# snow_depth_gauge_2B.net
KiCad netlist of a schematic drawn in EAGLE
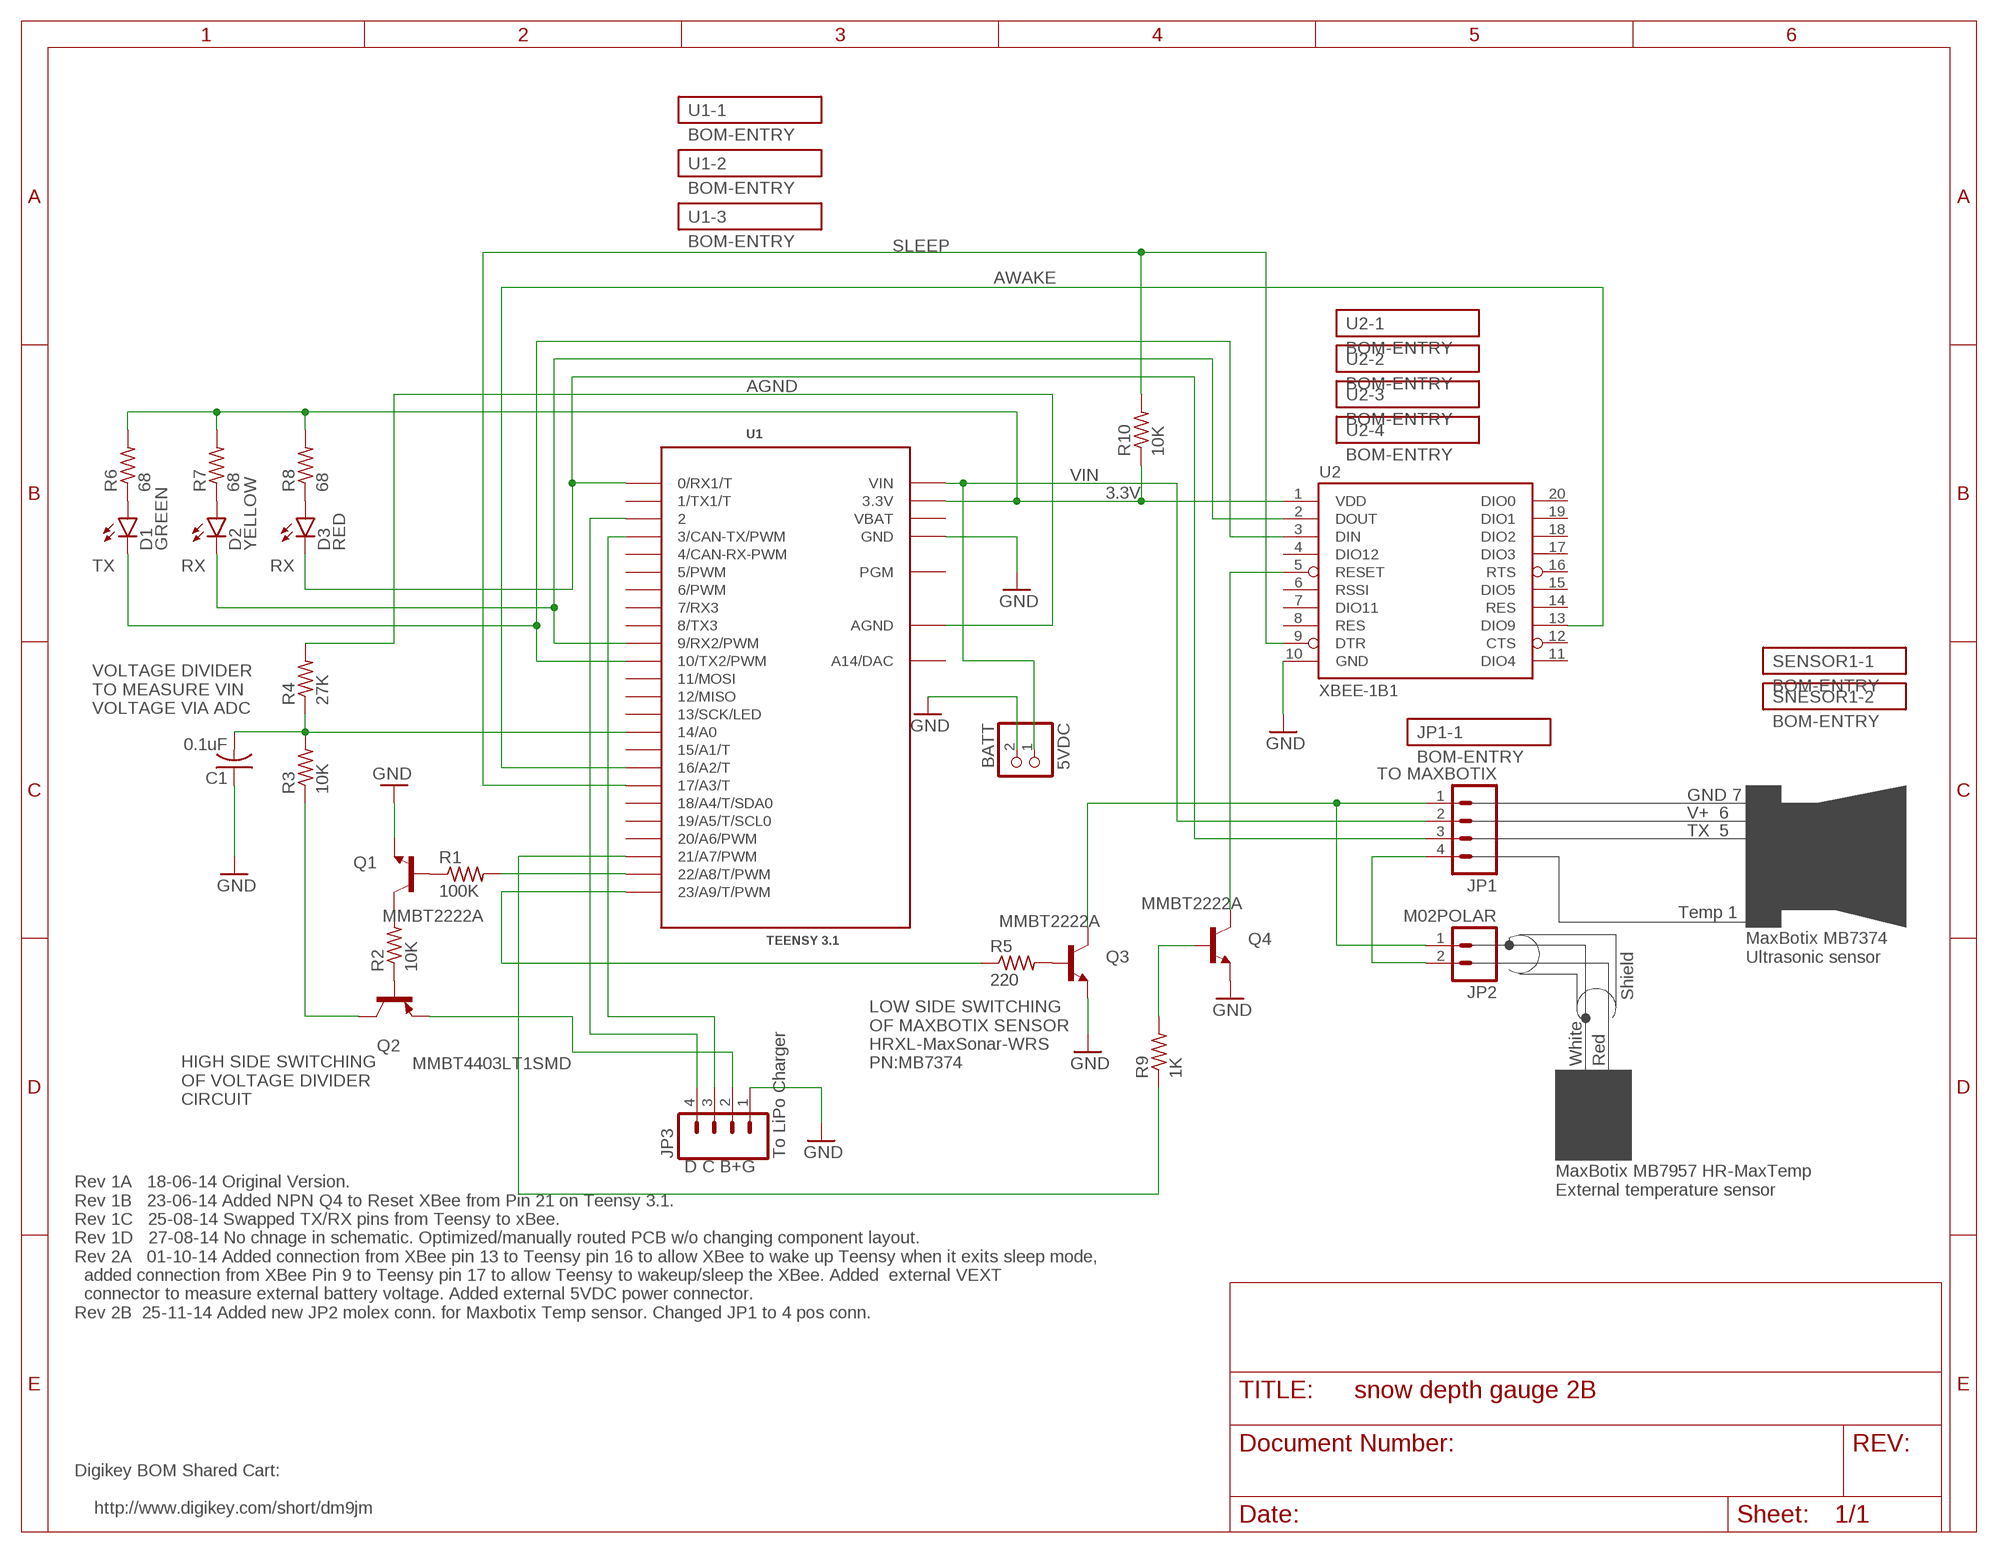
[diagram p0: schematic, sheet 1]

(export (version "E")
  (design (tool "Eeschema 10.0.6"))
  (components
    (comp (ref "BATT")
      (value "5VDC")
      (footprint "eagle-import:JST-PH-2-SMT-RA")
      (fields (field (name "PARTNO") "S2B-PH-SM4-TB(LF)(SN)"))
      (libsource (lib "eagle-import") (part "JST_2PIN-SMT-RA"))
    )
    (comp (ref "C1")
      (value "0.1uF")
      (footprint "eagle-import:C3216")
      (fields (field (name "PARTNO") "C1206C104K4RACTU"))
      (libsource (lib "eagle-import") (part "C-USC3216"))
    )
    (comp (ref "D1")
      (value "GREEN")
      (footprint "eagle-import:LED-0603")
      (fields (field (name "PARTNO") "LNJ337W83RA"))
      (libsource (lib "eagle-import") (part "LED-GREEN0603"))
    )
    (comp (ref "D2")
      (value "YELLOW")
      (footprint "eagle-import:LED-0603")
      (fields (field (name "PARTNO") "LNJ437W84RA"))
      (libsource (lib "eagle-import") (part "LED-YELLOW0603"))
    )
    (comp (ref "D3")
      (value "RED")
      (footprint "eagle-import:LED-0603")
      (fields (field (name "PARTNO") "LNJ237W82RA"))
      (libsource (lib "eagle-import") (part "LED-RED0603"))
    )
    (comp (ref "JP1")
      (value "TO MAXBOTIX")
      (footprint "eagle-import:MOLEX-1X4")
      (fields (field (name "PARTNO") "0022292041"))
      (libsource (lib "eagle-import") (part "M04POLAR"))
    )
    (comp (ref "JP2")
      (value "M02POLAR")
      (footprint "eagle-import:MOLEX-1X2")
      (fields (field (name "PARTNO") "0022292021"))
      (libsource (lib "eagle-import") (part "M02POLAR"))
    )
    (comp (ref "JP3")
      (value "To LiPo Charger")
      (footprint "eagle-import:MOLEX-1X4")
      (fields (field (name "PARTNO") "0022292041"))
      (libsource (lib "eagle-import") (part "M04POLAR"))
    )
    (comp (ref "Q1")
      (value "MMBT2222A")
      (footprint "eagle-import:SOT23-BEC")
      (libsource (lib "eagle-import") (part "-NPN-SOT23-BECMMBT2222ALT1"))
    )
    (comp (ref "Q2")
      (value "MMBT4403LT1SMD")
      (footprint "eagle-import:SOT23-BEC")
      (fields (field (name "PARTNO") "MMBT4403"))
      (libsource (lib "eagle-import") (part "MMBT4403SMDLT1"))
    )
    (comp (ref "Q3")
      (value "MMBT2222A")
      (footprint "eagle-import:SOT23-BEC")
      (libsource (lib "eagle-import") (part "-NPN-SOT23-BECMMBT2222ALT1"))
    )
    (comp (ref "Q4")
      (value "MMBT2222A")
      (footprint "eagle-import:SOT23-BEC")
      (libsource (lib "eagle-import") (part "-NPN-SOT23-BECMMBT2222ALT1"))
    )
    (comp (ref "R1")
      (value "100K")
      (footprint "eagle-import:R3216")
      (fields (field (name "PARTNO") "KTR18EZPJ104"))
      (libsource (lib "eagle-import") (part "R-US_R3216"))
    )
    (comp (ref "R2")
      (value "10K")
      (footprint "eagle-import:R3216")
      (fields (field (name "PARTNO") "KTR18EZPJ103"))
      (libsource (lib "eagle-import") (part "R-US_R3216"))
    )
    (comp (ref "R3")
      (value "10K")
      (footprint "eagle-import:R3216")
      (fields (field (name "PARTNO") "KTR18EZPJ103"))
      (libsource (lib "eagle-import") (part "R-US_R3216"))
    )
    (comp (ref "R4")
      (value "27K")
      (footprint "eagle-import:R3216")
      (fields (field (name "PARTNO") "KTR18EZPJ273"))
      (libsource (lib "eagle-import") (part "R-US_R3216"))
    )
    (comp (ref "R5")
      (value "220")
      (footprint "eagle-import:R3216")
      (fields (field (name "PARTNO") "KTR18EZPJ221"))
      (libsource (lib "eagle-import") (part "R-US_R3216"))
    )
    (comp (ref "R6")
      (value "68")
      (footprint "eagle-import:R3216")
      (fields (field (name "PARTNO") "KTR18EZPJ680"))
      (libsource (lib "eagle-import") (part "R-US_R3216"))
    )
    (comp (ref "R7")
      (value "68")
      (footprint "eagle-import:R3216")
      (fields (field (name "PARTNO") "KTR18EZPJ680"))
      (libsource (lib "eagle-import") (part "R-US_R3216"))
    )
    (comp (ref "R8")
      (value "68")
      (footprint "eagle-import:R3216")
      (fields (field (name "PARTNO") "KTR18EZPJ680"))
      (libsource (lib "eagle-import") (part "R-US_R3216"))
    )
    (comp (ref "R9")
      (value "1K")
      (footprint "eagle-import:R3216")
      (fields (field (name "PARTNO") "KTR18EZPJ102"))
      (libsource (lib "eagle-import") (part "R-US_R3216"))
    )
    (comp (ref "R10")
      (value "10K")
      (footprint "eagle-import:R3216")
      (fields (field (name "PARTNO") "KTR18EZPJ103"))
      (libsource (lib "eagle-import") (part "R-US_R3216"))
    )
    (comp (ref "U1")
      (value "TEENSY 3.1")
      (footprint "eagle-import:TEENSY_3.1_BASIC")
      (fields (field (name "PARTNO") "TEENSY31"))
      (libsource (lib "eagle-import") (part "TEENSY_3.1_BASIC"))
    )
    (comp (ref "U2")
      (value "XBEE-1B1")
      (footprint "eagle-import:XBEE-1")
      (fields (field (name "PARTNO") "XB24-AUI-001"))
      (libsource (lib "eagle-import") (part "XBEE-1B1"))
    )
  )
  (nets
    (net (code "1") (name "/3.3V") (class "Default")
      (node (ref "R10") (pin "1") (pinfunction "1_1") (pintype "passive"))
      (node (ref "R6") (pin "2") (pinfunction "2_2") (pintype "passive"))
      (node (ref "R7") (pin "2") (pinfunction "2_2") (pintype "passive"))
      (node (ref "R8") (pin "2") (pinfunction "2_2") (pintype "passive"))
      (node (ref "U1") (pin "3.3V") (pinfunction "3.3V_3.3V") (pintype "power_in"))
      (node (ref "U1") (pin "3.3V1") (pinfunction "3.3V_3.3V1") (pintype "power_in"))
      (node (ref "U2") (pin "1") (pinfunction "VDD_1") (pintype "power_in"))
    )
    (net (code "2") (name "/AGND") (class "Default")
      (node (ref "R4") (pin "2") (pinfunction "2_2") (pintype "passive"))
      (node (ref "U1") (pin "AGND") (pinfunction "AGND_AGND") (pintype "power_in"))
    )
    (net (code "3") (name "/AWAKE") (class "Default")
      (node (ref "U1") (pin "16/A2") (pinfunction "16/A2/T_16/A2") (pintype "bidirectional"))
      (node (ref "U2") (pin "13") (pinfunction "DIO9_13") (pintype "bidirectional"))
    )
    (net (code "4") (name "/SLEEP") (class "Default")
      (node (ref "R10") (pin "2") (pinfunction "2_2") (pintype "passive"))
      (node (ref "U1") (pin "17/A3") (pinfunction "17/A3/T_17/A3") (pintype "bidirectional"))
      (node (ref "U2") (pin "9") (pinfunction "DTR_9") (pintype "bidirectional"))
    )
    (net (code "5") (name "/VBAT") (class "Default")
      (node (ref "U1") (pin "VBAT") (pinfunction "VBAT_VBAT") (pintype "power_in"))
    )
    (net (code "6") (name "/VIN") (class "Default")
      (node (ref "BATT") (pin "1") (pinfunction "2_1") (pintype "passive"))
      (node (ref "JP1") (pin "2") (pinfunction "2_2") (pintype "passive"))
      (node (ref "U1") (pin "VIN") (pinfunction "VIN_VIN") (pintype "power_in"))
    )
    (net (code "7") (name "GND") (class "Default")
      (node (ref "BATT") (pin "2") (pinfunction "1_2") (pintype "passive"))
      (node (ref "C1") (pin "1") (pinfunction "1_1") (pintype "passive"))
      (node (ref "JP3") (pin "1") (pinfunction "1_1") (pintype "passive"))
      (node (ref "Q1") (pin "E") (pinfunction "E_E") (pintype "passive"))
      (node (ref "Q3") (pin "E") (pinfunction "E_E") (pintype "passive"))
      (node (ref "Q4") (pin "E") (pinfunction "E_E") (pintype "passive"))
      (node (ref "U1") (pin "GND") (pinfunction "GND_GND") (pintype "power_in"))
      (node (ref "U1") (pin "GND1") (pinfunction "GND_GND1") (pintype "power_in"))
      (node (ref "U2") (pin "10") (pinfunction "GND_10") (pintype "power_in"))
    )
    (net (code "8") (name "Net-(C1-Pad2)") (class "Default")
      (node (ref "C1") (pin "2") (pinfunction "2_2") (pintype "passive"))
      (node (ref "R3") (pin "2") (pinfunction "2_2") (pintype "passive"))
      (node (ref "R4") (pin "1") (pinfunction "1_1") (pintype "passive"))
      (node (ref "U1") (pin "14/A0") (pinfunction "14/A0_14/A0") (pintype "bidirectional"))
    )
    (net (code "9") (name "Net-(D1-PadA)") (class "Default")
      (node (ref "D1") (pin "A") (pinfunction "A_A") (pintype "passive"))
      (node (ref "R6") (pin "1") (pinfunction "1_1") (pintype "passive"))
    )
    (net (code "10") (name "Net-(D2-PadA)") (class "Default")
      (node (ref "D2") (pin "A") (pinfunction "A_A") (pintype "passive"))
      (node (ref "R7") (pin "1") (pinfunction "1_1") (pintype "passive"))
    )
    (net (code "11") (name "Net-(D3-PadA)") (class "Default")
      (node (ref "D3") (pin "A") (pinfunction "A_A") (pintype "passive"))
      (node (ref "R8") (pin "1") (pinfunction "1_1") (pintype "passive"))
    )
    (net (code "12") (name "Net-(JP1-Pad1)") (class "Default")
      (node (ref "JP1") (pin "1") (pinfunction "1_1") (pintype "passive"))
      (node (ref "JP2") (pin "1") (pinfunction "1_1") (pintype "passive"))
      (node (ref "Q3") (pin "C") (pinfunction "C_C") (pintype "passive"))
    )
    (net (code "13") (name "Net-(JP1-Pad4)") (class "Default")
      (node (ref "JP1") (pin "4") (pinfunction "4_4") (pintype "passive"))
      (node (ref "JP2") (pin "2") (pinfunction "2_2") (pintype "passive"))
    )
    (net (code "14") (name "Net-(JP3-Pad2)") (class "Default")
      (node (ref "JP3") (pin "2") (pinfunction "2_2") (pintype "passive"))
      (node (ref "Q2") (pin "E") (pinfunction "E_E") (pintype "passive"))
    )
    (net (code "15") (name "Net-(JP3-Pad4)") (class "Default")
      (node (ref "JP3") (pin "4") (pinfunction "4_4") (pintype "passive"))
      (node (ref "U1") (pin "2") (pinfunction "2_2") (pintype "bidirectional"))
    )
    (net (code "16") (name "Net-(Q1-PadB)") (class "Default")
      (node (ref "Q1") (pin "B") (pinfunction "B_B") (pintype "passive"))
      (node (ref "R1") (pin "1") (pinfunction "1_1") (pintype "passive"))
    )
    (net (code "17") (name "Net-(Q1-PadC)") (class "Default")
      (node (ref "Q1") (pin "C") (pinfunction "C_C") (pintype "passive"))
      (node (ref "R2") (pin "2") (pinfunction "2_2") (pintype "passive"))
    )
    (net (code "18") (name "Net-(Q2-PadB)") (class "Default")
      (node (ref "Q2") (pin "B") (pinfunction "B_B") (pintype "passive"))
      (node (ref "R2") (pin "1") (pinfunction "1_1") (pintype "passive"))
    )
    (net (code "19") (name "Net-(Q2-PadC)") (class "Default")
      (node (ref "Q2") (pin "C") (pinfunction "C_C") (pintype "passive"))
      (node (ref "R3") (pin "1") (pinfunction "1_1") (pintype "passive"))
    )
    (net (code "20") (name "Net-(Q3-PadB)") (class "Default")
      (node (ref "Q3") (pin "B") (pinfunction "B_B") (pintype "passive"))
      (node (ref "R5") (pin "2") (pinfunction "2_2") (pintype "passive"))
    )
    (net (code "21") (name "Net-(Q4-PadB)") (class "Default")
      (node (ref "Q4") (pin "B") (pinfunction "B_B") (pintype "passive"))
      (node (ref "R9") (pin "2") (pinfunction "2_2") (pintype "passive"))
    )
    (net (code "22") (name "Net-(U1-0{slash}RX1{slash}T)") (class "Default")
      (node (ref "D3") (pin "C") (pinfunction "C_C") (pintype "passive"))
      (node (ref "JP1") (pin "3") (pinfunction "3_3") (pintype "passive"))
      (node (ref "U1") (pin "0") (pinfunction "0/RX1/T_0") (pintype "bidirectional"))
    )
    (net (code "23") (name "Net-(U1-3{slash}CAN-TX{slash}PWM)") (class "Default")
      (node (ref "JP3") (pin "3") (pinfunction "3_3") (pintype "passive"))
      (node (ref "U1") (pin "3") (pinfunction "3/CAN-TX/PWM_3") (pintype "bidirectional"))
    )
    (net (code "24") (name "Net-(U1-9{slash}RX2{slash}PWM)") (class "Default")
      (node (ref "D2") (pin "C") (pinfunction "C_C") (pintype "passive"))
      (node (ref "U1") (pin "9") (pinfunction "9/RX2/PWM_9") (pintype "bidirectional"))
      (node (ref "U2") (pin "2") (pinfunction "DOUT_2") (pintype "output"))
    )
    (net (code "25") (name "Net-(U1-10{slash}TX2{slash}PWM)") (class "Default")
      (node (ref "D1") (pin "C") (pinfunction "C_C") (pintype "passive"))
      (node (ref "U1") (pin "10") (pinfunction "10/TX2/PWM_10") (pintype "bidirectional"))
      (node (ref "U2") (pin "3") (pinfunction "DIN_3") (pintype "input"))
    )
    (net (code "26") (name "Net-(U1-21{slash}A7{slash}PWM)") (class "Default")
      (node (ref "R9") (pin "1") (pinfunction "1_1") (pintype "passive"))
      (node (ref "U1") (pin "21/A7") (pinfunction "21/A7/PWM_21/A7") (pintype "bidirectional"))
    )
    (net (code "27") (name "Net-(U1-22{slash}A8{slash}T{slash}PWM)") (class "Default")
      (node (ref "R1") (pin "2") (pinfunction "2_2") (pintype "passive"))
      (node (ref "U1") (pin "22/A8") (pinfunction "22/A8/T/PWM_22/A8") (pintype "bidirectional"))
    )
    (net (code "28") (name "Net-(U1-23{slash}A9{slash}T{slash}PWM)") (class "Default")
      (node (ref "R5") (pin "1") (pinfunction "1_1") (pintype "passive"))
      (node (ref "U1") (pin "23/A9") (pinfunction "23/A9/T/PWM_23/A9") (pintype "bidirectional"))
    )
    (net (code "29") (name "Net-(U2-RESET)") (class "Default")
      (node (ref "Q4") (pin "C") (pinfunction "C_C") (pintype "passive"))
      (node (ref "U2") (pin "5") (pinfunction "RESET_5") (pintype "input"))
    )
    (net (code "30") (name "unconnected-(U1-1{slash}TX1{slash}T-Pad1)") (class "Default")
      (node (ref "U1") (pin "1") (pinfunction "1/TX1/T_1") (pintype "bidirectional"))
    )
    (net (code "31") (name "unconnected-(U1-4{slash}CAN-RX-PWM-Pad4)") (class "Default")
      (node (ref "U1") (pin "4") (pinfunction "4/CAN-RX-PWM_4") (pintype "bidirectional"))
    )
    (net (code "32") (name "unconnected-(U1-5{slash}PWM-Pad5)") (class "Default")
      (node (ref "U1") (pin "5") (pinfunction "5/PWM_5") (pintype "bidirectional"))
    )
    (net (code "33") (name "unconnected-(U1-6{slash}PWM-Pad6)") (class "Default")
      (node (ref "U1") (pin "6") (pinfunction "6/PWM_6") (pintype "bidirectional"))
    )
    (net (code "34") (name "unconnected-(U1-7{slash}RX3-Pad7)") (class "Default")
      (node (ref "U1") (pin "7") (pinfunction "7/RX3_7") (pintype "bidirectional"))
    )
    (net (code "35") (name "unconnected-(U1-8{slash}TX3-Pad8)") (class "Default")
      (node (ref "U1") (pin "8") (pinfunction "8/TX3_8") (pintype "bidirectional"))
    )
    (net (code "36") (name "unconnected-(U1-11{slash}MOSI-Pad11)") (class "Default")
      (node (ref "U1") (pin "11") (pinfunction "11/MOSI_11") (pintype "bidirectional"))
    )
    (net (code "37") (name "unconnected-(U1-12{slash}MISO-Pad12)") (class "Default")
      (node (ref "U1") (pin "12") (pinfunction "12/MISO_12") (pintype "bidirectional"))
    )
    (net (code "38") (name "unconnected-(U1-13{slash}SCK{slash}LED-Pad13)") (class "Default")
      (node (ref "U1") (pin "13") (pinfunction "13/SCK/LED_13") (pintype "bidirectional"))
    )
    (net (code "39") (name "unconnected-(U1-15{slash}A1{slash}T-Pad15{slash}A1)") (class "Default")
      (node (ref "U1") (pin "15/A1") (pinfunction "15/A1/T_15/A1") (pintype "bidirectional"))
    )
    (net (code "40") (name "unconnected-(U1-18{slash}A4{slash}T{slash}SDA0-Pad18{slash}A4)") (class "Default")
      (node (ref "U1") (pin "18/A4") (pinfunction "18/A4/T/SDA0_18/A4") (pintype "bidirectional"))
    )
    (net (code "41") (name "unconnected-(U1-19{slash}A5{slash}T{slash}SCL0-Pad19{slash}A5)") (class "Default")
      (node (ref "U1") (pin "19/A5") (pinfunction "19/A5/T/SCL0_19/A5") (pintype "bidirectional"))
    )
    (net (code "42") (name "unconnected-(U1-20{slash}A6{slash}PWM-Pad20{slash}A6)") (class "Default")
      (node (ref "U1") (pin "20/A6") (pinfunction "20/A6/PWM_20/A6") (pintype "bidirectional"))
    )
    (net (code "43") (name "unconnected-(U1-A14{slash}DAC-PadA14)") (class "Default")
      (node (ref "U1") (pin "A14") (pinfunction "A14/DAC_A14") (pintype "bidirectional"))
    )
    (net (code "44") (name "unconnected-(U1-PadPGM)") (class "Default")
      (node (ref "U1") (pin "PGM") (pinfunction "PGM_PGM") (pintype "bidirectional"))
    )
    (net (code "45") (name "unconnected-(U2-CTS-Pad12)") (class "Default")
      (node (ref "U2") (pin "12") (pinfunction "CTS_12") (pintype "output"))
    )
    (net (code "46") (name "unconnected-(U2-DIO0-Pad20)") (class "Default")
      (node (ref "U2") (pin "20") (pinfunction "DIO0_20") (pintype "bidirectional"))
    )
    (net (code "47") (name "unconnected-(U2-DIO1-Pad19)") (class "Default")
      (node (ref "U2") (pin "19") (pinfunction "DIO1_19") (pintype "bidirectional"))
    )
    (net (code "48") (name "unconnected-(U2-DIO2-Pad18)") (class "Default")
      (node (ref "U2") (pin "18") (pinfunction "DIO2_18") (pintype "bidirectional"))
    )
    (net (code "49") (name "unconnected-(U2-DIO3-Pad17)") (class "Default")
      (node (ref "U2") (pin "17") (pinfunction "DIO3_17") (pintype "bidirectional"))
    )
    (net (code "50") (name "unconnected-(U2-DIO4-Pad11)") (class "Default")
      (node (ref "U2") (pin "11") (pinfunction "DIO4_11") (pintype "bidirectional"))
    )
    (net (code "51") (name "unconnected-(U2-DIO5-Pad15)") (class "Default")
      (node (ref "U2") (pin "15") (pinfunction "DIO5_15") (pintype "bidirectional"))
    )
    (net (code "52") (name "unconnected-(U2-DIO11-Pad7)") (class "Default")
      (node (ref "U2") (pin "7") (pinfunction "DIO11_7") (pintype "bidirectional"))
    )
    (net (code "53") (name "unconnected-(U2-DIO12-Pad4)") (class "Default")
      (node (ref "U2") (pin "4") (pinfunction "DIO12_4") (pintype "bidirectional"))
    )
    (net (code "54") (name "unconnected-(U2-RES-Pad8)") (class "Default")
      (node (ref "U2") (pin "8") (pinfunction "RES_8") (pintype "bidirectional"))
    )
    (net (code "55") (name "unconnected-(U2-RES-Pad14)") (class "Default")
      (node (ref "U2") (pin "14") (pinfunction "RES_14") (pintype "bidirectional"))
    )
    (net (code "56") (name "unconnected-(U2-RSSI-Pad6)") (class "Default")
      (node (ref "U2") (pin "6") (pinfunction "RSSI_6") (pintype "bidirectional"))
    )
    (net (code "57") (name "unconnected-(U2-RTS-Pad16)") (class "Default")
      (node (ref "U2") (pin "16") (pinfunction "RTS_16") (pintype "input"))
    )
  )
)
